# SmartRock_EC_V4_small_4_3_3.net
KiCad netlist of a schematic drawn in EAGLE
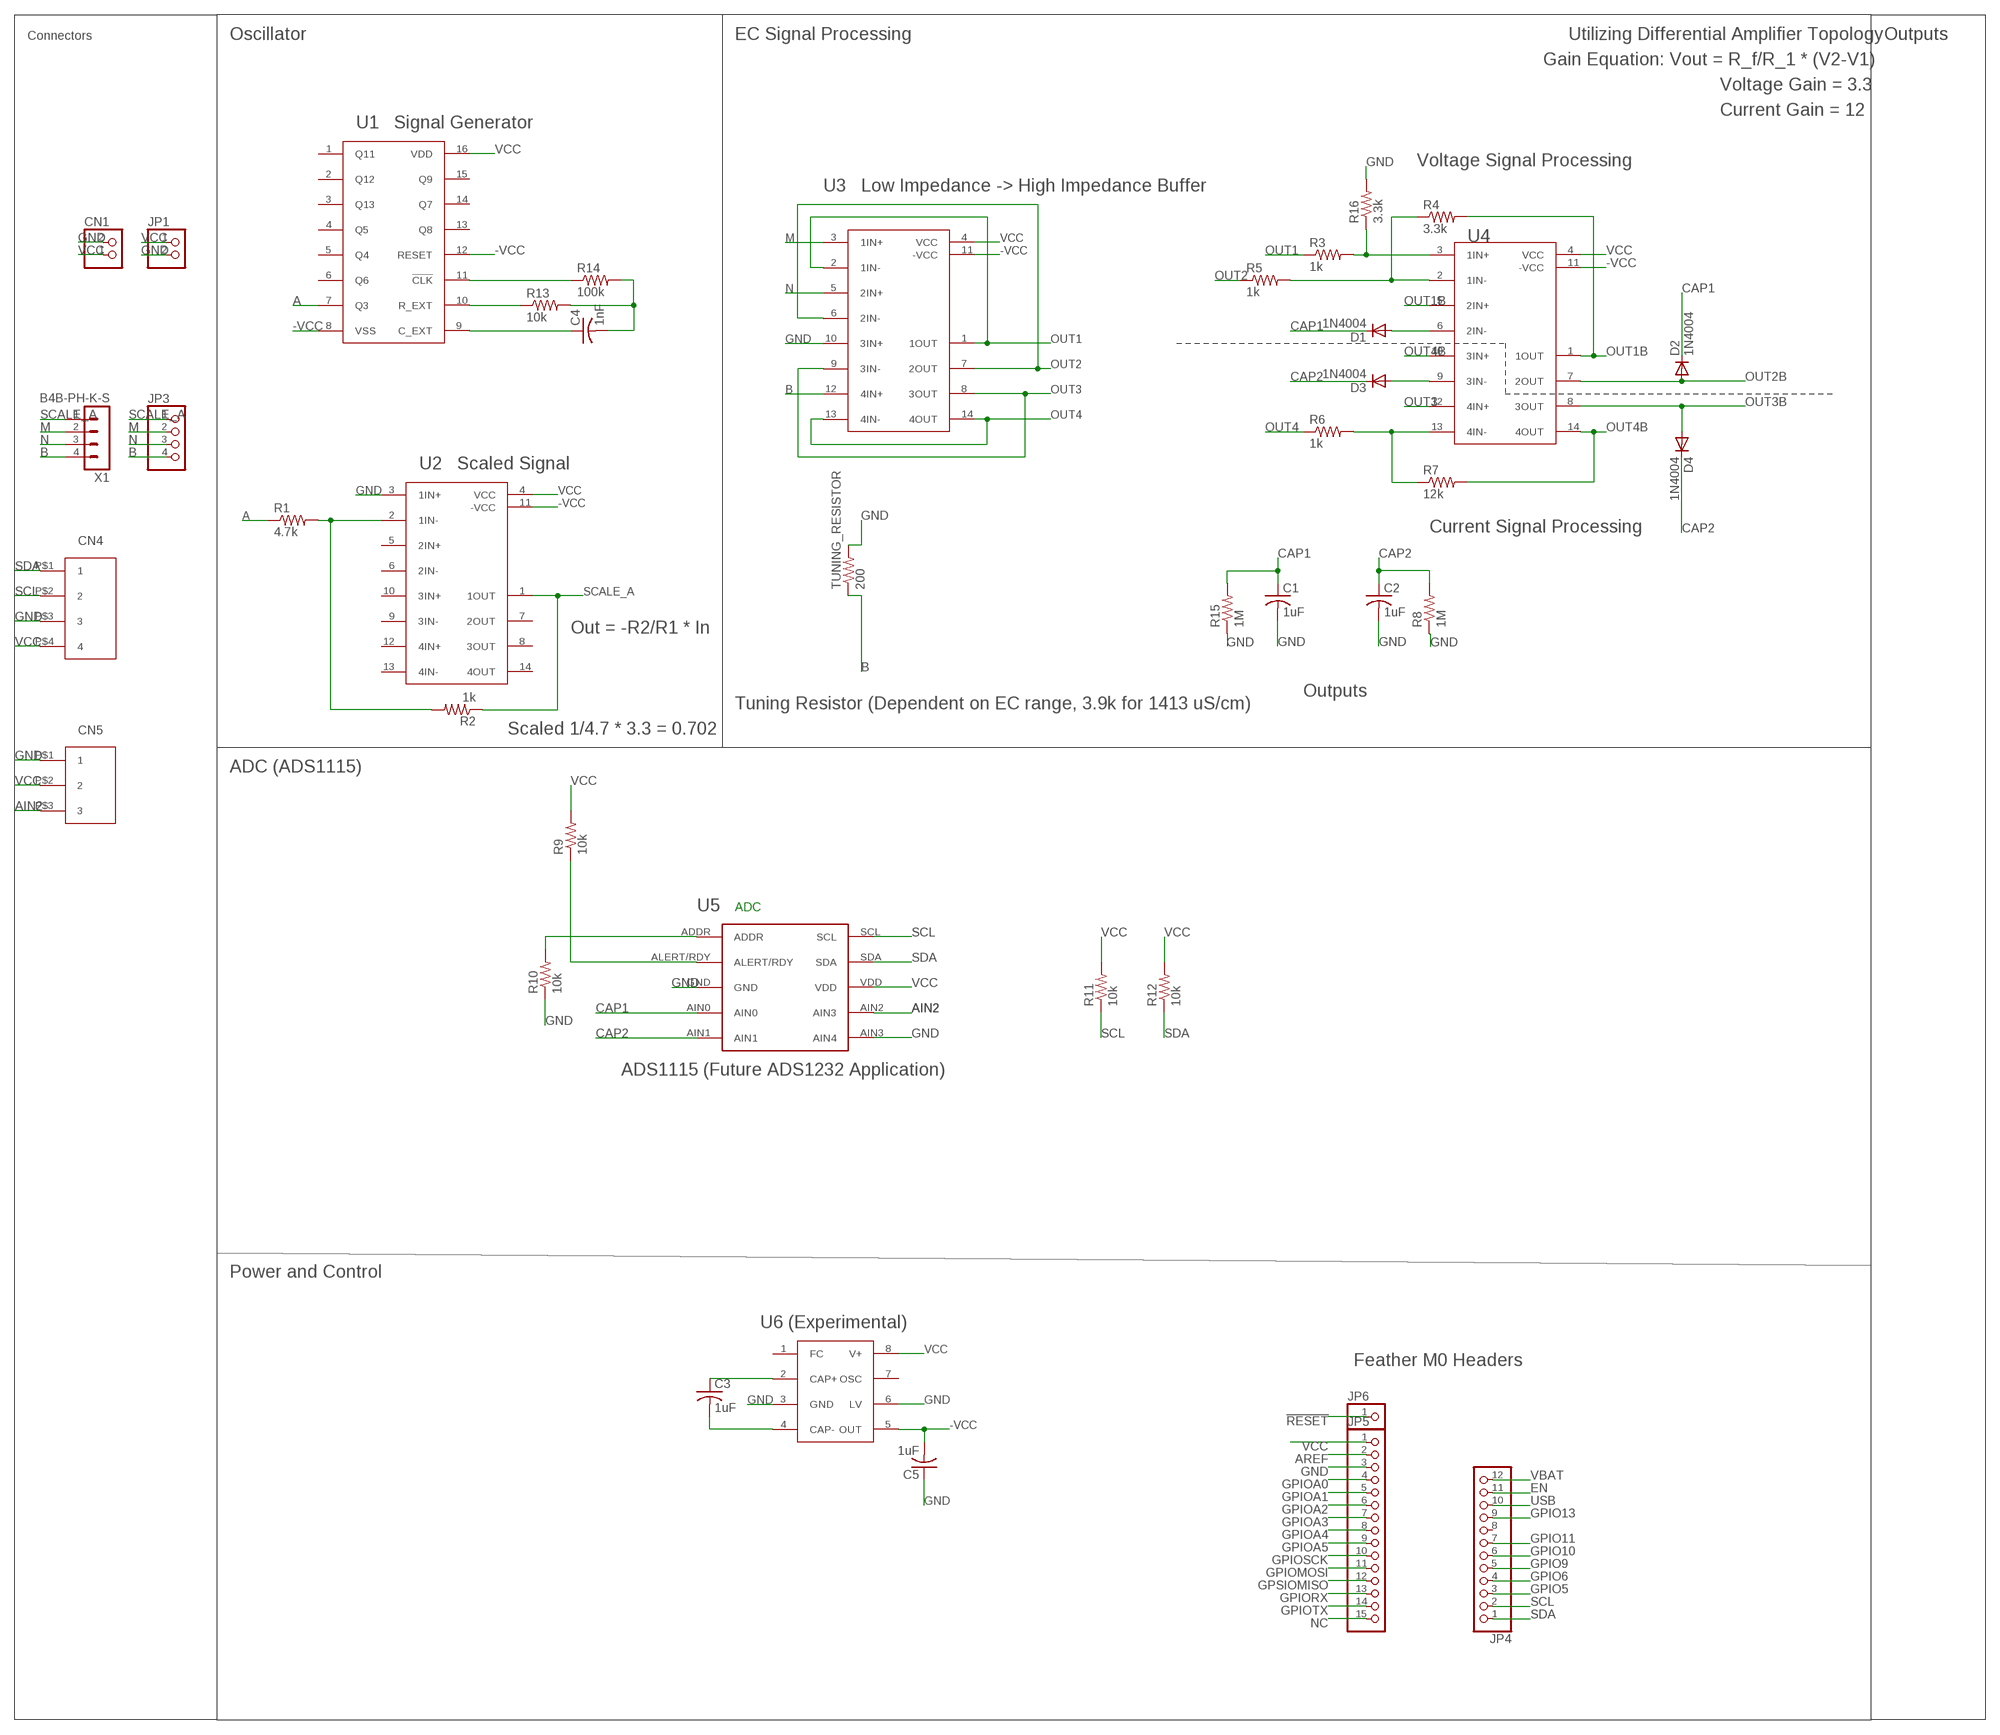
[diagram p0: schematic, sheet 1]

(export (version "E")
  (design (tool "Eeschema 10.0.6"))
  (components
    (comp (ref "C1")
      (value "1uF")
      (footprint "eagle-import:C025-024X044")
      (libsource (lib "eagle-import") (part "C-US025-024X044"))
    )
    (comp (ref "C2")
      (value "1uF")
      (footprint "eagle-import:C025-024X044")
      (libsource (lib "eagle-import") (part "C-US025-024X044"))
    )
    (comp (ref "C3")
      (value "1uF")
      (footprint "eagle-import:C025-024X044")
      (libsource (lib "eagle-import") (part "C-US025-024X044"))
    )
    (comp (ref "C4")
      (value "1nF")
      (footprint "eagle-import:C1206")
      (libsource (lib "eagle-import") (part "C-USC1206"))
    )
    (comp (ref "C5")
      (value "1uF")
      (footprint "eagle-import:C025-024X044")
      (libsource (lib "eagle-import") (part "C-US025-024X044"))
    )
    (comp (ref "CN1")
      (value "JST_2PIN-THM")
      (footprint "eagle-import:JST-PH-2-THM")
      (libsource (lib "eagle-import") (part "JST_2PIN-THM"))
    )
    (comp (ref "CN2")
      (value "JST_3PIN_2MM")
      (footprint "eagle-import:JST_3PIN_2MM")
      (libsource (lib "eagle-import") (part "JST_3PIN_2MM"))
    )
    (comp (ref "CN5")
      (value "JST_4PIN_2MM")
      (footprint "eagle-import:JST_4PIN_2MM")
      (libsource (lib "eagle-import") (part "JST_4PIN_2MM"))
    )
    (comp (ref "D1")
      (value "1N4004")
      (footprint "eagle-import:DO41-10")
      (libsource (lib "eagle-import") (part "1N4004"))
    )
    (comp (ref "D2")
      (value "1N4004")
      (footprint "eagle-import:DO41-10")
      (libsource (lib "eagle-import") (part "1N4004"))
    )
    (comp (ref "D3")
      (value "1N4004")
      (footprint "eagle-import:DO41-10")
      (libsource (lib "eagle-import") (part "1N4004"))
    )
    (comp (ref "D4")
      (value "1N4004")
      (footprint "eagle-import:DO41-10")
      (libsource (lib "eagle-import") (part "1N4004"))
    )
    (comp (ref "JP1")
      (value "PINHD-1X2")
      (footprint "eagle-import:1X02")
      (libsource (lib "eagle-import") (part "PINHD-1X2"))
    )
    (comp (ref "JP3")
      (value "PINHD-1X4")
      (footprint "eagle-import:1X04")
      (libsource (lib "eagle-import") (part "PINHD-1X4"))
    )
    (comp (ref "JP4")
      (value "PINHD-1X12-CB")
      (footprint "eagle-import:1X12-CB")
      (libsource (lib "eagle-import") (part "PINHD-1X12-CB"))
    )
    (comp (ref "JP5")
      (value "PINHD-1X15-CB")
      (footprint "eagle-import:1X15-CB")
      (libsource (lib "eagle-import") (part "PINHD-1X15-CB"))
    )
    (comp (ref "JP6")
      (value "PINHD-1X1CB")
      (footprint "eagle-import:1X01-CLEANBIG")
      (libsource (lib "eagle-import") (part "PINHD-1X1CB"))
    )
    (comp (ref "R1")
      (value "4.7k")
      (footprint "eagle-import:M1206")
      (libsource (lib "eagle-import") (part "R-US_M1206"))
    )
    (comp (ref "R2")
      (value "1k")
      (footprint "eagle-import:M1206")
      (libsource (lib "eagle-import") (part "R-US_M1206"))
    )
    (comp (ref "R3")
      (value "1k")
      (footprint "eagle-import:M1206")
      (libsource (lib "eagle-import") (part "R-US_M1206"))
    )
    (comp (ref "R4")
      (value "3.3k")
      (footprint "eagle-import:M1206")
      (libsource (lib "eagle-import") (part "R-US_M1206"))
    )
    (comp (ref "R5")
      (value "1k")
      (footprint "eagle-import:M1206")
      (libsource (lib "eagle-import") (part "R-US_M1206"))
    )
    (comp (ref "R6")
      (value "1k")
      (footprint "eagle-import:M1206")
      (libsource (lib "eagle-import") (part "R-US_M1206"))
    )
    (comp (ref "R7")
      (value "12k")
      (footprint "eagle-import:M1206")
      (libsource (lib "eagle-import") (part "R-US_M1206"))
    )
    (comp (ref "R8")
      (value "1M")
      (footprint "eagle-import:M1206")
      (libsource (lib "eagle-import") (part "R-US_M1206"))
    )
    (comp (ref "R9")
      (value "10k")
      (footprint "eagle-import:M1206")
      (libsource (lib "eagle-import") (part "R-US_M1206"))
    )
    (comp (ref "R10")
      (value "10k")
      (footprint "eagle-import:M1206")
      (libsource (lib "eagle-import") (part "R-US_M1206"))
    )
    (comp (ref "R11")
      (value "10k")
      (footprint "eagle-import:M1206")
      (libsource (lib "eagle-import") (part "R-US_M1206"))
    )
    (comp (ref "R12")
      (value "10k")
      (footprint "eagle-import:M1206")
      (libsource (lib "eagle-import") (part "R-US_M1206"))
    )
    (comp (ref "R13")
      (value "10k")
      (footprint "eagle-import:M1206")
      (libsource (lib "eagle-import") (part "R-US_M1206"))
    )
    (comp (ref "R14")
      (value "100k")
      (footprint "eagle-import:M1206")
      (libsource (lib "eagle-import") (part "R-US_M1206"))
    )
    (comp (ref "R15")
      (value "1M")
      (footprint "eagle-import:M1206")
      (libsource (lib "eagle-import") (part "R-US_M1206"))
    )
    (comp (ref "R16")
      (value "3.3k")
      (footprint "eagle-import:M1206")
      (libsource (lib "eagle-import") (part "R-US_M1206"))
    )
    (comp (ref "TUNING_RESISTOR")
      (value "200")
      (footprint "eagle-import:M1206")
      (libsource (lib "eagle-import") (part "R-US_M1206"))
    )
    (comp (ref "U1")
      (value "CD4060BPWR")
      (footprint "eagle-import:CD4060BPWR")
      (libsource (lib "eagle-import") (part "CD4060BPWR"))
    )
    (comp (ref "U2")
      (value "TL074CPWR")
      (footprint "eagle-import:LT074CPWR")
      (libsource (lib "eagle-import") (part "TL074CPWR"))
    )
    (comp (ref "U3")
      (value "TL074CPWR")
      (footprint "eagle-import:LT074CPWR")
      (libsource (lib "eagle-import") (part "TL074CPWR"))
    )
    (comp (ref "U4")
      (value "TL074CPWR")
      (footprint "eagle-import:LT074CPWR")
      (libsource (lib "eagle-import") (part "TL074CPWR"))
    )
    (comp (ref "U5")
      (value "ADS1115")
      (footprint "eagle-import:ADS1115")
      (libsource (lib "eagle-import") (part "ADS1115"))
    )
    (comp (ref "U6+")
      (value "MAX660MX/NOPB")
      (footprint "eagle-import:MAX660MX_NOPB")
      (libsource (lib "eagle-import") (part "MAX660MX/NOPB"))
    )
    (comp (ref "X1")
      (value "B4B-PH-K-S")
      (footprint "eagle-import:B4B-PH-K-S")
      (libsource (lib "eagle-import") (part "B4B-PH-K-S"))
    )
  )
  (nets
    (net (code "1") (name "/-VCC") (class "Default")
      (node (ref "C5") (pin "2") (pinfunction "2_2") (pintype "passive"))
      (node (ref "U1") (pin "12") (pinfunction "RESET_12") (pintype "bidirectional"))
      (node (ref "U1") (pin "8") (pinfunction "VSS_8") (pintype "bidirectional"))
      (node (ref "U2") (pin "11") (pinfunction "-VCC_11") (pintype "bidirectional"))
      (node (ref "U3") (pin "11") (pinfunction "-VCC_11") (pintype "bidirectional"))
      (node (ref "U4") (pin "11") (pinfunction "-VCC_11") (pintype "bidirectional"))
      (node (ref "U6+") (pin "5") (pinfunction "OUT_5") (pintype "bidirectional"))
    )
    (net (code "2") (name "/A") (class "Default")
      (node (ref "R1") (pin "1") (pinfunction "1_1") (pintype "passive"))
      (node (ref "U1") (pin "7") (pinfunction "Q3_7") (pintype "bidirectional"))
    )
    (net (code "3") (name "/AIN2") (class "Default")
      (node (ref "CN2") (pin "P$3") (pinfunction "3_P$3") (pintype "bidirectional"))
      (node (ref "U5") (pin "AIN2") (pinfunction "AIN3_AIN2") (pintype "bidirectional"))
    )
    (net (code "4") (name "/AREF") (class "Default")
      (node (ref "JP5") (pin "2") (pinfunction "2_2") (pintype "passive"))
    )
    (net (code "5") (name "/B") (class "Default")
      (node (ref "JP3") (pin "4") (pinfunction "4_4") (pintype "passive"))
      (node (ref "TUNING_RESISTOR") (pin "1") (pinfunction "1_1") (pintype "passive"))
      (node (ref "U3") (pin "12") (pinfunction "4IN+_12") (pintype "bidirectional"))
      (node (ref "X1") (pin "4") (pinfunction "4_4") (pintype "passive"))
    )
    (net (code "6") (name "/CAP1") (class "Default")
      (node (ref "C1") (pin "1") (pinfunction "1_1") (pintype "passive"))
      (node (ref "D1") (pin "C") (pinfunction "C_C") (pintype "passive"))
      (node (ref "D2") (pin "C") (pinfunction "C_C") (pintype "passive"))
      (node (ref "R15") (pin "2") (pinfunction "2_2") (pintype "passive"))
      (node (ref "U5") (pin "AIN0") (pinfunction "AIN0_AIN0") (pintype "bidirectional"))
    )
    (net (code "7") (name "/CAP2") (class "Default")
      (node (ref "C2") (pin "1") (pinfunction "1_1") (pintype "passive"))
      (node (ref "D3") (pin "C") (pinfunction "C_C") (pintype "passive"))
      (node (ref "D4") (pin "C") (pinfunction "C_C") (pintype "passive"))
      (node (ref "R8") (pin "2") (pinfunction "2_2") (pintype "passive"))
      (node (ref "U5") (pin "AIN1") (pinfunction "AIN1_AIN1") (pintype "bidirectional"))
    )
    (net (code "8") (name "/EN") (class "Default")
      (node (ref "JP4") (pin "11") (pinfunction "11_11") (pintype "passive"))
    )
    (net (code "9") (name "/GND") (class "Default")
      (node (ref "C1") (pin "2") (pinfunction "2_2") (pintype "passive"))
      (node (ref "C2") (pin "2") (pinfunction "2_2") (pintype "passive"))
      (node (ref "C5") (pin "1") (pinfunction "1_1") (pintype "passive"))
      (node (ref "CN1") (pin "2") (pinfunction "1_2") (pintype "passive"))
      (node (ref "CN2") (pin "P$1") (pinfunction "1_P$1") (pintype "bidirectional"))
      (node (ref "CN5") (pin "P$3") (pinfunction "3_P$3") (pintype "bidirectional"))
      (node (ref "JP1") (pin "2") (pinfunction "2_2") (pintype "passive"))
      (node (ref "JP5") (pin "3") (pinfunction "3_3") (pintype "passive"))
      (node (ref "R10") (pin "1") (pinfunction "1_1") (pintype "passive"))
      (node (ref "R15") (pin "1") (pinfunction "1_1") (pintype "passive"))
      (node (ref "R16") (pin "2") (pinfunction "2_2") (pintype "passive"))
      (node (ref "R8") (pin "1") (pinfunction "1_1") (pintype "passive"))
      (node (ref "TUNING_RESISTOR") (pin "2") (pinfunction "2_2") (pintype "passive"))
      (node (ref "U2") (pin "3") (pinfunction "1IN+_3") (pintype "bidirectional"))
      (node (ref "U3") (pin "10") (pinfunction "3IN+_10") (pintype "bidirectional"))
      (node (ref "U5") (pin "AIN3") (pinfunction "AIN4_AIN3") (pintype "bidirectional"))
      (node (ref "U5") (pin "GND") (pinfunction "GND_GND") (pintype "bidirectional"))
      (node (ref "U6+") (pin "3") (pinfunction "GND_3") (pintype "bidirectional"))
      (node (ref "U6+") (pin "6") (pinfunction "LV_6") (pintype "bidirectional"))
    )
    (net (code "10") (name "/GPIO5") (class "Default")
      (node (ref "JP4") (pin "3") (pinfunction "3_3") (pintype "passive"))
    )
    (net (code "11") (name "/GPIO6") (class "Default")
      (node (ref "JP4") (pin "4") (pinfunction "4_4") (pintype "passive"))
    )
    (net (code "12") (name "/GPIO9") (class "Default")
      (node (ref "JP4") (pin "5") (pinfunction "5_5") (pintype "passive"))
    )
    (net (code "13") (name "/GPIO10") (class "Default")
      (node (ref "JP4") (pin "6") (pinfunction "6_6") (pintype "passive"))
    )
    (net (code "14") (name "/GPIO11") (class "Default")
      (node (ref "JP4") (pin "7") (pinfunction "7_7") (pintype "passive"))
    )
    (net (code "15") (name "/GPIO13") (class "Default")
      (node (ref "JP4") (pin "9") (pinfunction "9_9") (pintype "passive"))
    )
    (net (code "16") (name "/GPIOA0") (class "Default")
      (node (ref "JP5") (pin "4") (pinfunction "4_4") (pintype "passive"))
    )
    (net (code "17") (name "/GPIOA1") (class "Default")
      (node (ref "JP5") (pin "5") (pinfunction "5_5") (pintype "passive"))
    )
    (net (code "18") (name "/GPIOA2") (class "Default")
      (node (ref "JP5") (pin "6") (pinfunction "6_6") (pintype "passive"))
    )
    (net (code "19") (name "/GPIOA3") (class "Default")
      (node (ref "JP5") (pin "7") (pinfunction "7_7") (pintype "passive"))
    )
    (net (code "20") (name "/GPIOA4") (class "Default")
      (node (ref "JP5") (pin "8") (pinfunction "8_8") (pintype "passive"))
    )
    (net (code "21") (name "/GPIOA5") (class "Default")
      (node (ref "JP5") (pin "9") (pinfunction "9_9") (pintype "passive"))
    )
    (net (code "22") (name "/GPIOMOSI") (class "Default")
      (node (ref "JP5") (pin "11") (pinfunction "11_11") (pintype "passive"))
    )
    (net (code "23") (name "/GPIORX") (class "Default")
      (node (ref "JP5") (pin "13") (pinfunction "13_13") (pintype "passive"))
    )
    (net (code "24") (name "/GPIOSCK") (class "Default")
      (node (ref "JP5") (pin "10") (pinfunction "10_10") (pintype "passive"))
    )
    (net (code "25") (name "/GPIOTX") (class "Default")
      (node (ref "JP5") (pin "14") (pinfunction "14_14") (pintype "passive"))
    )
    (net (code "26") (name "/GPSIOMISO") (class "Default")
      (node (ref "JP5") (pin "12") (pinfunction "12_12") (pintype "passive"))
    )
    (net (code "27") (name "/M") (class "Default")
      (node (ref "JP3") (pin "2") (pinfunction "2_2") (pintype "passive"))
      (node (ref "U3") (pin "3") (pinfunction "1IN+_3") (pintype "bidirectional"))
      (node (ref "X1") (pin "2") (pinfunction "2_2") (pintype "passive"))
    )
    (net (code "28") (name "/N") (class "Default")
      (node (ref "JP3") (pin "3") (pinfunction "3_3") (pintype "passive"))
      (node (ref "U3") (pin "5") (pinfunction "2IN+_5") (pintype "bidirectional"))
      (node (ref "X1") (pin "3") (pinfunction "3_3") (pintype "passive"))
    )
    (net (code "29") (name "/NC") (class "Default")
      (node (ref "JP5") (pin "15") (pinfunction "15_15") (pintype "passive"))
    )
    (net (code "30") (name "/OUT1") (class "Default")
      (node (ref "R3") (pin "1") (pinfunction "1_1") (pintype "passive"))
      (node (ref "U3") (pin "1") (pinfunction "1OUT_1") (pintype "bidirectional"))
      (node (ref "U3") (pin "2") (pinfunction "1IN-_2") (pintype "bidirectional"))
    )
    (net (code "31") (name "/OUT1B") (class "Default")
      (node (ref "R4") (pin "2") (pinfunction "2_2") (pintype "passive"))
      (node (ref "U4") (pin "1") (pinfunction "1OUT_1") (pintype "bidirectional"))
      (node (ref "U4") (pin "5") (pinfunction "2IN+_5") (pintype "bidirectional"))
    )
    (net (code "32") (name "/OUT2") (class "Default")
      (node (ref "R5") (pin "1") (pinfunction "1_1") (pintype "passive"))
      (node (ref "U3") (pin "6") (pinfunction "2IN-_6") (pintype "bidirectional"))
      (node (ref "U3") (pin "7") (pinfunction "2OUT_7") (pintype "bidirectional"))
    )
    (net (code "33") (name "/OUT2B") (class "Default")
      (node (ref "D2") (pin "A") (pinfunction "A_A") (pintype "passive"))
      (node (ref "U4") (pin "7") (pinfunction "2OUT_7") (pintype "bidirectional"))
    )
    (net (code "34") (name "/OUT3") (class "Default")
      (node (ref "U3") (pin "8") (pinfunction "3OUT_8") (pintype "bidirectional"))
      (node (ref "U3") (pin "9") (pinfunction "3IN-_9") (pintype "bidirectional"))
      (node (ref "U4") (pin "12") (pinfunction "4IN+_12") (pintype "bidirectional"))
    )
    (net (code "35") (name "/OUT3B") (class "Default")
      (node (ref "D4") (pin "A") (pinfunction "A_A") (pintype "passive"))
      (node (ref "U4") (pin "8") (pinfunction "3OUT_8") (pintype "bidirectional"))
    )
    (net (code "36") (name "/OUT4") (class "Default")
      (node (ref "R6") (pin "1") (pinfunction "1_1") (pintype "passive"))
      (node (ref "U3") (pin "13") (pinfunction "4IN-_13") (pintype "bidirectional"))
      (node (ref "U3") (pin "14") (pinfunction "4OUT_14") (pintype "bidirectional"))
    )
    (net (code "37") (name "/OUT4B") (class "Default")
      (node (ref "R7") (pin "2") (pinfunction "2_2") (pintype "passive"))
      (node (ref "U4") (pin "10") (pinfunction "3IN+_10") (pintype "bidirectional"))
      (node (ref "U4") (pin "14") (pinfunction "4OUT_14") (pintype "bidirectional"))
    )
    (net (code "38") (name "/SCALE_A") (class "Default")
      (node (ref "JP3") (pin "1") (pinfunction "1_1") (pintype "passive"))
      (node (ref "R2") (pin "1") (pinfunction "1_1") (pintype "passive"))
      (node (ref "U2") (pin "1") (pinfunction "1OUT_1") (pintype "bidirectional"))
      (node (ref "X1") (pin "1") (pinfunction "1_1") (pintype "passive"))
    )
    (net (code "39") (name "/SCL") (class "Default")
      (node (ref "CN5") (pin "P$2") (pinfunction "2_P$2") (pintype "bidirectional"))
      (node (ref "JP4") (pin "2") (pinfunction "2_2") (pintype "passive"))
      (node (ref "R11") (pin "1") (pinfunction "1_1") (pintype "passive"))
      (node (ref "U5") (pin "SCL") (pinfunction "SCL_SCL") (pintype "bidirectional"))
    )
    (net (code "40") (name "/SDA") (class "Default")
      (node (ref "CN5") (pin "P$1") (pinfunction "1_P$1") (pintype "bidirectional"))
      (node (ref "JP4") (pin "1") (pinfunction "1_1") (pintype "passive"))
      (node (ref "R12") (pin "1") (pinfunction "1_1") (pintype "passive"))
      (node (ref "U5") (pin "SDA") (pinfunction "SDA_SDA") (pintype "bidirectional"))
    )
    (net (code "41") (name "/USB") (class "Default")
      (node (ref "JP4") (pin "10") (pinfunction "10_10") (pintype "passive"))
    )
    (net (code "42") (name "/VBAT") (class "Default")
      (node (ref "JP4") (pin "12") (pinfunction "12_12") (pintype "passive"))
    )
    (net (code "43") (name "/VCC") (class "Default")
      (node (ref "CN1") (pin "1") (pinfunction "2_1") (pintype "passive"))
      (node (ref "CN2") (pin "P$2") (pinfunction "2_P$2") (pintype "bidirectional"))
      (node (ref "CN5") (pin "P$4") (pinfunction "4_P$4") (pintype "bidirectional"))
      (node (ref "JP1") (pin "1") (pinfunction "1_1") (pintype "passive"))
      (node (ref "JP5") (pin "1") (pinfunction "1_1") (pintype "passive"))
      (node (ref "R11") (pin "2") (pinfunction "2_2") (pintype "passive"))
      (node (ref "R12") (pin "2") (pinfunction "2_2") (pintype "passive"))
      (node (ref "R9") (pin "2") (pinfunction "2_2") (pintype "passive"))
      (node (ref "U1") (pin "16") (pinfunction "VDD_16") (pintype "bidirectional"))
      (node (ref "U2") (pin "4") (pinfunction "VCC_4") (pintype "bidirectional"))
      (node (ref "U3") (pin "4") (pinfunction "VCC_4") (pintype "bidirectional"))
      (node (ref "U4") (pin "4") (pinfunction "VCC_4") (pintype "bidirectional"))
      (node (ref "U5") (pin "VDD") (pinfunction "VDD_VDD") (pintype "bidirectional"))
      (node (ref "U6+") (pin "8") (pinfunction "V+_8") (pintype "bidirectional"))
    )
    (net (code "44") (name "/~{RESET}") (class "Default")
      (node (ref "JP6") (pin "1") (pinfunction "1_1") (pintype "passive"))
    )
    (net (code "45") (name "Net-(C4-Pad2)") (class "Default")
      (node (ref "C4") (pin "2") (pinfunction "2_2") (pintype "passive"))
      (node (ref "R13") (pin "2") (pinfunction "2_2") (pintype "passive"))
      (node (ref "R14") (pin "2") (pinfunction "2_2") (pintype "passive"))
    )
    (net (code "46") (name "Net-(R9-Pad1)") (class "Default")
      (node (ref "R9") (pin "1") (pinfunction "1_1") (pintype "passive"))
      (node (ref "U5") (pin "ALERT/RDY") (pinfunction "ALERT/RDY_ALERT/RDY") (pintype "bidirectional"))
    )
    (net (code "47") (name "Net-(R10-Pad2)") (class "Default")
      (node (ref "R10") (pin "2") (pinfunction "2_2") (pintype "passive"))
      (node (ref "U5") (pin "ADDR") (pinfunction "ADDR_ADDR") (pintype "bidirectional"))
    )
    (net (code "48") (name "Net-(U1-C_EXT)") (class "Default")
      (node (ref "C4") (pin "1") (pinfunction "1_1") (pintype "passive"))
      (node (ref "U1") (pin "9") (pinfunction "C_EXT_9") (pintype "bidirectional"))
    )
    (net (code "49") (name "Net-(U1-R_EXT)") (class "Default")
      (node (ref "R13") (pin "1") (pinfunction "1_1") (pintype "passive"))
      (node (ref "U1") (pin "10") (pinfunction "R_EXT_10") (pintype "bidirectional"))
    )
    (net (code "50") (name "Net-(U1-~{CLK})") (class "Default")
      (node (ref "R14") (pin "1") (pinfunction "1_1") (pintype "passive"))
      (node (ref "U1") (pin "11") (pinfunction "~{CLK}_11") (pintype "bidirectional"))
    )
    (net (code "51") (name "Net-(U2-1IN-)") (class "Default")
      (node (ref "R1") (pin "2") (pinfunction "2_2") (pintype "passive"))
      (node (ref "R2") (pin "2") (pinfunction "2_2") (pintype "passive"))
      (node (ref "U2") (pin "2") (pinfunction "1IN-_2") (pintype "bidirectional"))
    )
    (net (code "52") (name "Net-(U4-1IN+)") (class "Default")
      (node (ref "R16") (pin "1") (pinfunction "1_1") (pintype "passive"))
      (node (ref "R3") (pin "2") (pinfunction "2_2") (pintype "passive"))
      (node (ref "U4") (pin "3") (pinfunction "1IN+_3") (pintype "bidirectional"))
    )
    (net (code "53") (name "Net-(U4-1IN-)") (class "Default")
      (node (ref "R4") (pin "1") (pinfunction "1_1") (pintype "passive"))
      (node (ref "R5") (pin "2") (pinfunction "2_2") (pintype "passive"))
      (node (ref "U4") (pin "2") (pinfunction "1IN-_2") (pintype "bidirectional"))
    )
    (net (code "54") (name "Net-(U4-2IN-)") (class "Default")
      (node (ref "D1") (pin "A") (pinfunction "A_A") (pintype "passive"))
      (node (ref "U4") (pin "6") (pinfunction "2IN-_6") (pintype "bidirectional"))
    )
    (net (code "55") (name "Net-(U4-3IN-)") (class "Default")
      (node (ref "D3") (pin "A") (pinfunction "A_A") (pintype "passive"))
      (node (ref "U4") (pin "9") (pinfunction "3IN-_9") (pintype "bidirectional"))
    )
    (net (code "56") (name "Net-(U4-4IN-)") (class "Default")
      (node (ref "R6") (pin "2") (pinfunction "2_2") (pintype "passive"))
      (node (ref "R7") (pin "1") (pinfunction "1_1") (pintype "passive"))
      (node (ref "U4") (pin "13") (pinfunction "4IN-_13") (pintype "bidirectional"))
    )
    (net (code "57") (name "Net-(U6+-CAP+)") (class "Default")
      (node (ref "C3") (pin "1") (pinfunction "1_1") (pintype "passive"))
      (node (ref "U6+") (pin "2") (pinfunction "CAP+_2") (pintype "bidirectional"))
    )
    (net (code "58") (name "Net-(U6+-CAP-)") (class "Default")
      (node (ref "C3") (pin "2") (pinfunction "2_2") (pintype "passive"))
      (node (ref "U6+") (pin "4") (pinfunction "CAP-_4") (pintype "bidirectional"))
    )
    (net (code "59") (name "unconnected-(JP4-Pad8)") (class "Default")
      (node (ref "JP4") (pin "8") (pinfunction "8_8") (pintype "passive"))
    )
    (net (code "60") (name "unconnected-(U1-Q4-Pad5)") (class "Default")
      (node (ref "U1") (pin "5") (pinfunction "Q4_5") (pintype "bidirectional"))
    )
    (net (code "61") (name "unconnected-(U1-Q5-Pad4)") (class "Default")
      (node (ref "U1") (pin "4") (pinfunction "Q5_4") (pintype "bidirectional"))
    )
    (net (code "62") (name "unconnected-(U1-Q6-Pad6)") (class "Default")
      (node (ref "U1") (pin "6") (pinfunction "Q6_6") (pintype "bidirectional"))
    )
    (net (code "63") (name "unconnected-(U1-Q7-Pad14)") (class "Default")
      (node (ref "U1") (pin "14") (pinfunction "Q7_14") (pintype "bidirectional"))
    )
    (net (code "64") (name "unconnected-(U1-Q8-Pad13)") (class "Default")
      (node (ref "U1") (pin "13") (pinfunction "Q8_13") (pintype "bidirectional"))
    )
    (net (code "65") (name "unconnected-(U1-Q9-Pad15)") (class "Default")
      (node (ref "U1") (pin "15") (pinfunction "Q9_15") (pintype "bidirectional"))
    )
    (net (code "66") (name "unconnected-(U1-Q11-Pad1)") (class "Default")
      (node (ref "U1") (pin "1") (pinfunction "Q11_1") (pintype "bidirectional"))
    )
    (net (code "67") (name "unconnected-(U1-Q12-Pad2)") (class "Default")
      (node (ref "U1") (pin "2") (pinfunction "Q12_2") (pintype "bidirectional"))
    )
    (net (code "68") (name "unconnected-(U1-Q13-Pad3)") (class "Default")
      (node (ref "U1") (pin "3") (pinfunction "Q13_3") (pintype "bidirectional"))
    )
    (net (code "69") (name "unconnected-(U2-2IN+-Pad5)") (class "Default")
      (node (ref "U2") (pin "5") (pinfunction "2IN+_5") (pintype "bidirectional"))
    )
    (net (code "70") (name "unconnected-(U2-2IN--Pad6)") (class "Default")
      (node (ref "U2") (pin "6") (pinfunction "2IN-_6") (pintype "bidirectional"))
    )
    (net (code "71") (name "unconnected-(U2-2OUT-Pad7)") (class "Default")
      (node (ref "U2") (pin "7") (pinfunction "2OUT_7") (pintype "bidirectional"))
    )
    (net (code "72") (name "unconnected-(U2-3IN+-Pad10)") (class "Default")
      (node (ref "U2") (pin "10") (pinfunction "3IN+_10") (pintype "bidirectional"))
    )
    (net (code "73") (name "unconnected-(U2-3IN--Pad9)") (class "Default")
      (node (ref "U2") (pin "9") (pinfunction "3IN-_9") (pintype "bidirectional"))
    )
    (net (code "74") (name "unconnected-(U2-3OUT-Pad8)") (class "Default")
      (node (ref "U2") (pin "8") (pinfunction "3OUT_8") (pintype "bidirectional"))
    )
    (net (code "75") (name "unconnected-(U2-4IN+-Pad12)") (class "Default")
      (node (ref "U2") (pin "12") (pinfunction "4IN+_12") (pintype "bidirectional"))
    )
    (net (code "76") (name "unconnected-(U2-4IN--Pad13)") (class "Default")
      (node (ref "U2") (pin "13") (pinfunction "4IN-_13") (pintype "bidirectional"))
    )
    (net (code "77") (name "unconnected-(U2-4OUT-Pad14)") (class "Default")
      (node (ref "U2") (pin "14") (pinfunction "4OUT_14") (pintype "bidirectional"))
    )
    (net (code "78") (name "unconnected-(U6+-FC-Pad1)") (class "Default")
      (node (ref "U6+") (pin "1") (pinfunction "FC_1") (pintype "bidirectional"))
    )
    (net (code "79") (name "unconnected-(U6+-OSC-Pad7)") (class "Default")
      (node (ref "U6+") (pin "7") (pinfunction "OSC_7") (pintype "bidirectional"))
    )
  )
)
